# Boost_LM5123.net
KiCad netlist of a schematic drawn in Altium Designer
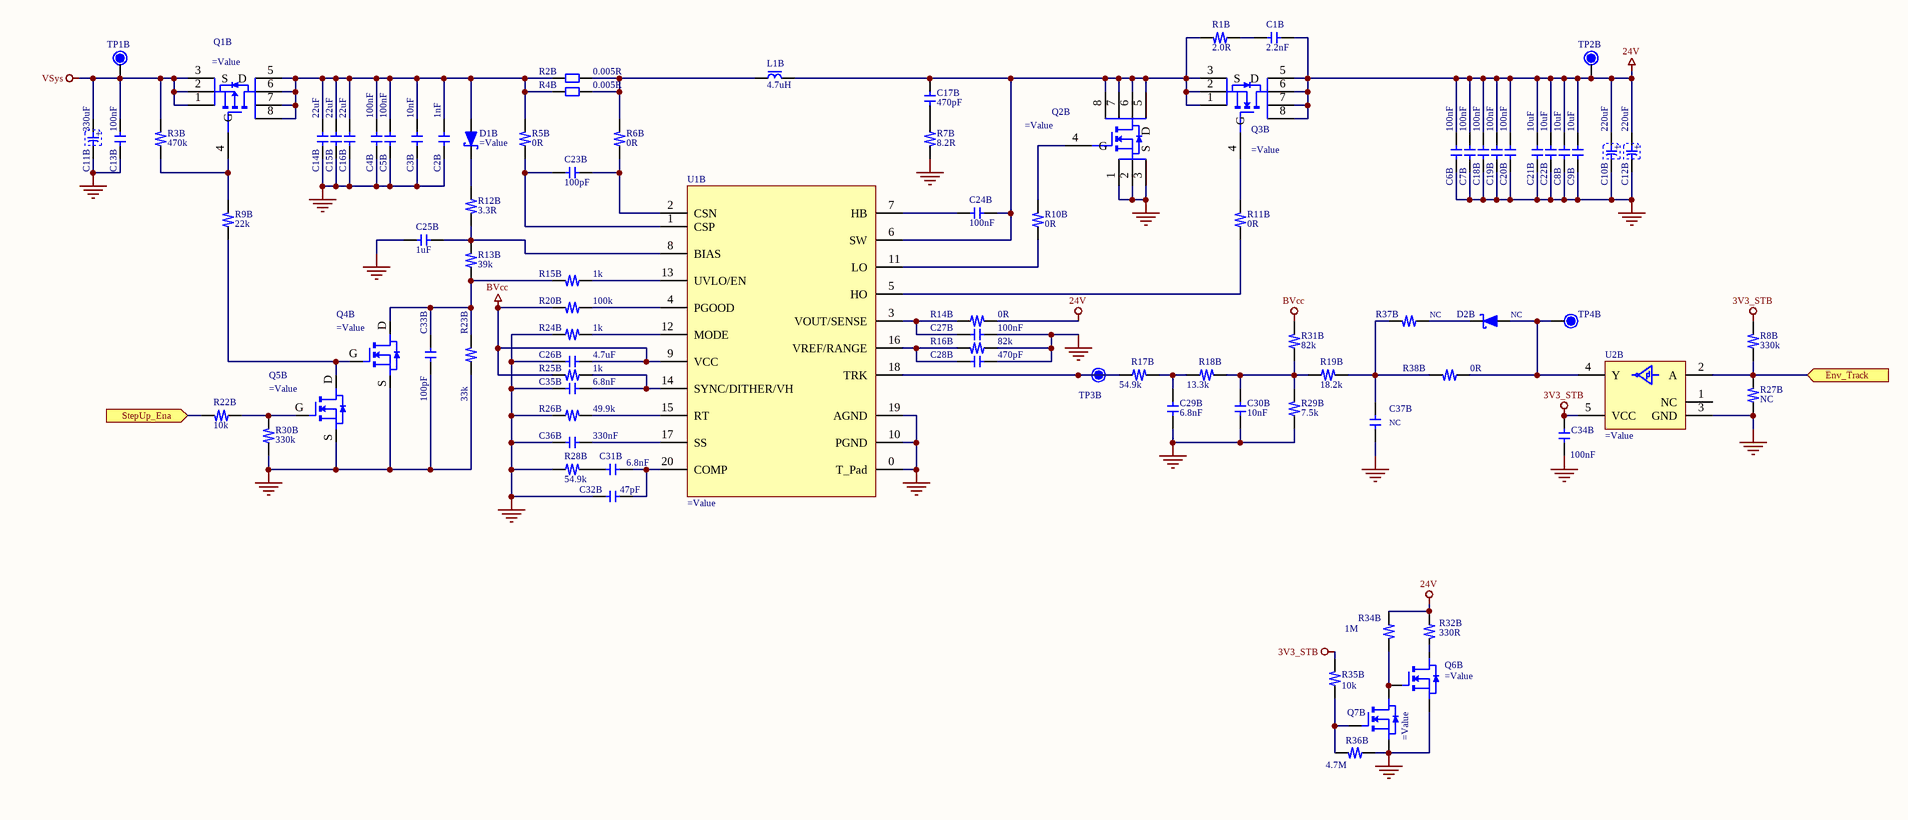
[diagram p0: Boost_LM5123.SchDoc]

(export (version "E")
  (design (tool "Eeschema 10.0.6"))
  (components
    (comp (ref "C1B")
      (value "2.2nF")
      (footprint "C0603X100")
      (description "PSHF SMD M CAP 2.2nF 50V ±10% 0603 X7R")
      (fields (field (name "MANUFACTURER") "Multi Sourced") (field (name "TOLERANCE") "±10%"))
      (libsource (lib "altium-import") (part "root_2_CAP1_"))
    )
    (comp (ref "C2B")
      (value "1nF")
      (footprint "C0603X100")
      (description "PSHF SMD M CAP 1nF 50V ±10% 0603 X7R")
      (fields (field (name "MANUFACTURER") "Multi Sourced") (field (name "TOLERANCE") "±10%"))
      (libsource (lib "altium-import") (part "root_1_CAP1_"))
    )
    (comp (ref "C3B")
      (value "10nF")
      (footprint "C0603X100")
      (description "PSHF SMD M CAP 10nF 50V ±10% 0603 X7R")
      (fields (field (name "MANUFACTURER") "Multi Sourced") (field (name "TOLERANCE") "±10%"))
      (libsource (lib "altium-import") (part "root_1_CAP1_"))
    )
    (comp (ref "C4B")
      (value "100nF")
      (footprint "C0603X100")
      (description "PSHF SMD M CAP 100nF 25V ±10% 0603 X7R")
      (fields (field (name "MANUFACTURER") "Multi Sourced") (field (name "TOLERANCE") "±10%"))
      (libsource (lib "altium-import") (part "root_3_CAP1_"))
    )
    (comp (ref "C5B")
      (value "100nF")
      (footprint "C0603X100")
      (description "PSHF SMD M CAP 100nF 25V ±10% 0603 X7R")
      (fields (field (name "MANUFACTURER") "Multi Sourced") (field (name "TOLERANCE") "±10%"))
      (libsource (lib "altium-import") (part "root_3_CAP1_"))
    )
    (comp (ref "C6B")
      (value "100nF")
      (footprint "C0603X100")
      (description "PSHF SMD M CAP 100nF 50V ±10% 0603 X7R")
      (fields (field (name "MANUFACTURER") "Multi Sourced") (field (name "TOLERANCE") "±10%"))
      (libsource (lib "altium-import") (part "root_1_CAP1_"))
    )
    (comp (ref "C7B")
      (value "100nF")
      (footprint "C0603X100")
      (description "PSHF SMD M CAP 100nF 50V ±10% 0603 X7R")
      (fields (field (name "MANUFACTURER") "Multi Sourced") (field (name "TOLERANCE") "±10%"))
      (libsource (lib "altium-import") (part "root_1_CAP1_"))
    )
    (comp (ref "C8B")
      (value "10uF")
      (footprint "C1206")
      (description "PSHF SMD M CAP 10uF 50V ±10% 1206 X5R")
      (fields (field (name "MANUFACTURER") "Multi Sourced") (field (name "TOLERANCE") "±10%"))
      (libsource (lib "altium-import") (part "root_1_CAP1_"))
    )
    (comp (ref "C9B")
      (value "10uF")
      (footprint "C1206")
      (description "PSHF SMD M CAP 10uF 50V ±10% 1206 X5R")
      (fields (field (name "MANUFACTURER") "Multi Sourced") (field (name "TOLERANCE") "±10%"))
      (libsource (lib "altium-import") (part "root_1_CAP1_"))
    )
    (comp (ref "C10B")
      (value "220uF")
      (footprint "ECAP_SMD_800X1000")
      (description "SMD COND ELECT 220μF 35V ±20% 105°C SHOUKE")
      (fields (field (name "MANUFACTURER") "Multi-Sourced") (field (name "TOLERANCE") "±20%"))
      (libsource (lib "altium-import") (part "root_3_ECAP2_"))
    )
    (comp (ref "C11B")
      (value "330uF")
      (footprint "E_CAP_SMD_10%2A10.2")
      (description "GPHF SMD COND ELECT 330μF 35V ±20% -40-+105℃ 10x10.5mm")
      (fields (field (name "MANUFACTURER") "Multi-Sourced") (field (name "TOLERANCE") "±20%"))
      (libsource (lib "altium-import") (part "root_3_ECAP2_"))
    )
    (comp (ref "C12B")
      (value "220uF")
      (footprint "ECAP_SMD_800X1000")
      (description "SMD COND ELECT 220μF 35V ±20% 105°C SHOUKE")
      (fields (field (name "MANUFACTURER") "Multi-Sourced") (field (name "TOLERANCE") "±20%"))
      (libsource (lib "altium-import") (part "root_3_ECAP2_"))
    )
    (comp (ref "C13B")
      (value "100nF")
      (footprint "C0603X100")
      (description "PSHF SMD M CAP 100nF 25V ±10% 0603 X7R")
      (fields (field (name "MANUFACTURER") "Multi Sourced") (field (name "TOLERANCE") "±10%"))
      (libsource (lib "altium-import") (part "root_1_CAP1_"))
    )
    (comp (ref "C14B")
      (value "22uF")
      (footprint "C1206")
      (description "PSHF SMD M CAP 22uF 25V ±20% 1206 X5R")
      (fields (field (name "MANUFACTURER") "Multi Sourced") (field (name "TOLERANCE") "±20%"))
      (libsource (lib "altium-import") (part "root_1_CAP1_"))
    )
    (comp (ref "C15B")
      (value "22uF")
      (footprint "C1206")
      (description "PSHF SMD M CAP 22uF 25V ±20% 1206 X5R")
      (fields (field (name "MANUFACTURER") "Multi Sourced") (field (name "TOLERANCE") "±20%"))
      (libsource (lib "altium-import") (part "root_1_CAP1_"))
    )
    (comp (ref "C16B")
      (value "22uF")
      (footprint "C1206")
      (description "PSHF SMD M CAP 22uF 25V ±20% 1206 X5R")
      (fields (field (name "MANUFACTURER") "Multi Sourced") (field (name "TOLERANCE") "±20%"))
      (libsource (lib "altium-import") (part "root_1_CAP1_"))
    )
    (comp (ref "C17B")
      (value "470pF")
      (footprint "C0603X80")
      (description "PSHF SMD M CAP 470pF 50V ±5% 0603 NPO")
      (fields (field (name "MANUFACTURER") "Multi Sourced") (field (name "TOLERANCE") "±5%"))
      (libsource (lib "altium-import") (part "root_3_CAP1_"))
    )
    (comp (ref "C18B")
      (value "100nF")
      (footprint "C0603X100")
      (description "PSHF SMD M CAP 100nF 50V ±10% 0603 X7R")
      (fields (field (name "MANUFACTURER") "Multi Sourced") (field (name "TOLERANCE") "±10%"))
      (libsource (lib "altium-import") (part "root_1_CAP1_"))
    )
    (comp (ref "C19B")
      (value "100nF")
      (footprint "C0603X100")
      (description "PSHF SMD M CAP 100nF 50V ±10% 0603 X7R")
      (fields (field (name "MANUFACTURER") "Multi Sourced") (field (name "TOLERANCE") "±10%"))
      (libsource (lib "altium-import") (part "root_1_CAP1_"))
    )
    (comp (ref "C20B")
      (value "100nF")
      (footprint "C0603X100")
      (description "PSHF SMD M CAP 100nF 50V ±10% 0603 X7R")
      (fields (field (name "MANUFACTURER") "Multi Sourced") (field (name "TOLERANCE") "±10%"))
      (libsource (lib "altium-import") (part "root_1_CAP1_"))
    )
    (comp (ref "C21B")
      (value "10uF")
      (footprint "C1206")
      (description "PSHF SMD M CAP 10uF 50V ±10% 1206 X5R")
      (fields (field (name "MANUFACTURER") "Multi Sourced") (field (name "TOLERANCE") "±10%"))
      (libsource (lib "altium-import") (part "root_1_CAP1_"))
    )
    (comp (ref "C22B")
      (value "10uF")
      (footprint "C1206")
      (description "PSHF SMD M CAP 10uF 50V ±10% 1206 X5R")
      (fields (field (name "MANUFACTURER") "Multi Sourced") (field (name "TOLERANCE") "±10%"))
      (libsource (lib "altium-import") (part "root_1_CAP1_"))
    )
    (comp (ref "C23B")
      (value "100pF")
      (footprint "C0603X80")
      (description "PSHF SMD M CAP 100pF 50V ±10% 0603 X7R")
      (fields (field (name "MANUFACTURER") "Multi Sourced") (field (name "TOLERANCE") "±10%"))
      (libsource (lib "altium-import") (part "root_0_CAP1_"))
    )
    (comp (ref "C24B")
      (value "100nF")
      (footprint "C0603X100")
      (description "GPHF SMD M CAP 100nF 50V ±10% 0603 X7R")
      (fields (field (name "MANUFACTURER") "Multi Sourced") (field (name "TOLERANCE") "±10%"))
      (libsource (lib "altium-import") (part "root_2_CAP1_"))
    )
    (comp (ref "C25B")
      (value "1uF")
      (footprint "C0603X105")
      (description "PSHF SMD M CAP 1uF 25V ±10% 0603 X7R")
      (fields (field (name "MANUFACTURER") "Multi Sourced") (field (name "TOLERANCE") "±10%"))
      (libsource (lib "altium-import") (part "root_2_CAP1_"))
    )
    (comp (ref "C26B")
      (value "4.7uF")
      (footprint "C0805_145")
      (description "PSHF SMD M CAP 4.7uF 25V ±10% 0805 X7R")
      (fields (field (name "MANUFACTURER") "Multi Sourced") (field (name "TOLERANCE") "±10%"))
      (libsource (lib "altium-import") (part "root_2_CAP1_"))
    )
    (comp (ref "C27B")
      (value "100nF")
      (footprint "C0603X100")
      (description "GPHF SMD M CAP 100nF 50V ±10% 0603 X7R")
      (fields (field (name "MANUFACTURER") "Multi Sourced") (field (name "TOLERANCE") "±10%"))
      (libsource (lib "altium-import") (part "root_0_CAP1_"))
    )
    (comp (ref "C28B")
      (value "470pF")
      (footprint "C0603X80")
      (description "PSHF SMD M CAP 470pF 50V ±5% 0603 NPO")
      (fields (field (name "MANUFACTURER") "Multi Sourced") (field (name "TOLERANCE") "±5%"))
      (libsource (lib "altium-import") (part "root_0_CAP1_"))
    )
    (comp (ref "C29B")
      (value "6.8nF")
      (footprint "C0603X100")
      (description "PSHF SMD M CAP 6.8nF 50V ±10% 0603 X7R")
      (fields (field (name "MANUFACTURER") "Multi Sourced") (field (name "TOLERANCE") "±10%"))
      (libsource (lib "altium-import") (part "root_3_CAP1_"))
    )
    (comp (ref "C30B")
      (value "10nF")
      (footprint "C0603X100")
      (description "PSHF SMD M CAP 10nF 50V ±10% 0603 X7R")
      (fields (field (name "MANUFACTURER") "Multi Sourced") (field (name "TOLERANCE") "±10%"))
      (libsource (lib "altium-import") (part "root_3_CAP1_"))
    )
    (comp (ref "C31B")
      (value "6.8nF")
      (footprint "C0603X100")
      (description "PSHF SMD M CAP 6.8nF 50V ±10% 0603 X7R")
      (fields (field (name "MANUFACTURER") "Multi Sourced") (field (name "TOLERANCE") "±10%"))
      (libsource (lib "altium-import") (part "root_0_CAP1_"))
    )
    (comp (ref "C32B")
      (value "47pF")
      (footprint "C0603X80")
      (description "PSHF SMD M CAP 47pF 50V ±5% 0603 NPO")
      (fields (field (name "MANUFACTURER") "Multi Sourced") (field (name "TOLERANCE") "±5%"))
      (libsource (lib "altium-import") (part "root_2_CAP1_"))
    )
    (comp (ref "C33B")
      (value "100pF")
      (footprint "C0603X80")
      (description "PSHF SMD M CAP 100pF 50V ±10% 0603 X7R")
      (fields (field (name "MANUFACTURER") "Multi Sourced") (field (name "TOLERANCE") "±10%"))
      (libsource (lib "altium-import") (part "root_3_CAP1_"))
    )
    (comp (ref "C34B")
      (value "100nF")
      (footprint "C0603X100")
      (description "PSHF SMD M CAP 100nF 25V ±10% 0603 X7R")
      (fields (field (name "MANUFACTURER") "Multi Sourced") (field (name "TOLERANCE") "±10%"))
      (libsource (lib "altium-import") (part "root_1_CAP1_"))
    )
    (comp (ref "C35B")
      (value "6.8nF")
      (footprint "C0603X100")
      (description "PSHF SMD M CAP 6.8nF 50V ±10% 0603 X7R")
      (fields (field (name "MANUFACTURER") "Multi Sourced") (field (name "TOLERANCE") "±10%"))
      (libsource (lib "altium-import") (part "root_2_CAP1_"))
    )
    (comp (ref "C36B")
      (value "330nF")
      (footprint "C0603X105")
      (description "SMD M CAP 330nF 50V ±10% 0603 X7R")
      (fields (field (name "MANUFACTURER") "Multi Sourced") (field (name "TOLERANCE") "±10%"))
      (libsource (lib "altium-import") (part "root_2_CAP1_"))
    )
    (comp (ref "C37B")
      (value "1uF")
      (footprint "C0603X105")
      (description "GPHF SMD M CAP 1uF 10V ±10% 0603 X7R")
      (fields (field (name "TOLERANCE") "±10%") (field (name "MANUFACTURER") "Multi Sourced"))
      (libsource (lib "altium-import") (part "root_1_CAP1_"))
    )
    (comp (ref "D1B")
      (value "~")
      (footprint "SOD-123")
      (description "PS SMD DIODE 2P SOD-123 B5819W CJ")
      (fields (field (name "MANUFACTURER") "[CJ]") (field (name "VOLTAGE") "40V"))
      (libsource (lib "altium-import") (part "root_3_DIODE_SCHOTTKY1_"))
    )
    (comp (ref "D2B")
      (value "~")
      (footprint "SOD-323")
      (description "GP SMD DIODE 2P 30V SOD323 BAT54WS PANJIT")
      (fields (field (name "MANUFACTURER") "PANJIT") (field (name "VOLTAGE") "30V"))
      (libsource (lib "altium-import") (part "root_0_mirrored_DIODE_SCHOTTKY1_"))
    )
    (comp (ref "L1B")
      (value "4.7uH")
      (footprint "IND_SMD_YT_SQU_L135XW126XH57")
      (description "SMD INDUCTOR 4.7μH 100KHz NORM")
      (fields (field (name "MANUFACTURER") "CET CHAMPI") (field (name "TOLERANCE") "7:20%"))
      (libsource (lib "altium-import") (part "root_0_INDUCTOR1_"))
    )
    (comp (ref "Q1B")
      (value "~")
      (footprint "DFN8_500X600X100_127_A")
      (description "SMD FET 8P 30V PDFN5x6-8L JMTG080P03A JJW")
      (fields (field (name "MANUFACTURER") "JJW") (field (name "VOLTAGE") "30"))
      (libsource (lib "altium-import") (part "root_1_mirrored_P-MOS2_8Pin_"))
    )
    (comp (ref "Q2B")
      (value "~")
      (footprint "DFN8_500X600X100_127_A")
      (description "SMD FET 8P 40V PDFN5x6-8L JMTG60N04B JJW")
      (fields (field (name "MANUFACTURER") "JJW") (field (name "VOLTAGE") "40"))
      (libsource (lib "altium-import") (part "root_0_N-MOS2_8Pin_"))
    )
    (comp (ref "Q3B")
      (value "~")
      (footprint "DFN8_500X600X100_127_A")
      (description "SMD FET 8P 40V PDFN5x6-8L JMTG60N04B JJW")
      (fields (field (name "MANUFACTURER") "JJW") (field (name "VOLTAGE") "40"))
      (libsource (lib "altium-import") (part "root_1_mirrored_N-MOS2_8Pin_"))
    )
    (comp (ref "Q4B")
      (value "~")
      (footprint "SOT23-GSD")
      (description "GP SMD FET 3P SOT23 2N7002K CTE")
      (fields (field (name "MANUFACTURER") "CTE") (field (name "VOLTAGE") "60V"))
      (libsource (lib "") (part "root_0_N-MOS1__1"))
    )
    (comp (ref "Q5B")
      (value "~")
      (footprint "SOT23-GSD")
      (description "GP SMD FET 3P SOT23 2N7002K CTE")
      (fields (field (name "MANUFACTURER") "CTE") (field (name "VOLTAGE") "60V"))
      (libsource (lib "") (part "root_0_N-MOS1__1"))
    )
    (comp (ref "Q6B")
      (value "~")
      (footprint "SOT23-GSD")
      (description "GP SMD FET 3P SOT23 2N7002K CTE")
      (fields (field (name "MANUFACTURER") "CTE") (field (name "VOLTAGE") "60V"))
      (libsource (lib "altium-import") (part "root_0_N-MOS1_"))
    )
    (comp (ref "Q7B")
      (value "~")
      (footprint "SOT23-GSD")
      (description "GP SMD FET 3P SOT23 2N7002K CTE")
      (fields (field (name "MANUFACTURER") "CTE") (field (name "VOLTAGE") "60V"))
      (libsource (lib "altium-import") (part "root_0_N-MOS1_"))
    )
    (comp (ref "R1B")
      (value "2.0R")
      (footprint "R0805")
      (description "PS SMD RES. 2OHM 1/8W 5% 0805")
      (fields (field (name "TOLERANCE") "1%") (field (name "MANUFACTURER") "Multi-Sourced"))
      (libsource (lib "altium-import") (part "root_0_RES1_"))
    )
    (comp (ref "R2B")
      (value "0.005R")
      (footprint "R1206")
      (description "SMD METAL FILM RES. 5mohm 1W 1% 1206 WALTER")
      (fields (field (name "TOLERANCE") "1%") (field (name "MANUFACTURER") "WALTER"))
      (libsource (lib "altium-import") (part "root_0_RES4_"))
    )
    (comp (ref "R3B")
      (value "470k")
      (footprint "R0603")
      (description "PS SMD RES. 470KOHM 1/10W 1% 0603")
      (fields (field (name "TOLERANCE") "1%") (field (name "MANUFACTURER") "Multi-Sourced"))
      (libsource (lib "altium-import") (part "root_3_RES1_"))
    )
    (comp (ref "R4B")
      (value "0.005R")
      (footprint "R1206")
      (description "SMD METAL FILM RES. 5mohm 1W 1% 1206 WALTER")
      (fields (field (name "TOLERANCE") "1%") (field (name "MANUFACTURER") "WALTER"))
      (libsource (lib "altium-import") (part "root_0_RES4_"))
    )
    (comp (ref "R5B")
      (value "0R")
      (footprint "R0603")
      (description "PS SMD RES. 0OHM 1/10W 5% 0603")
      (fields (field (name "TOLERANCE") "1%") (field (name "MANUFACTURER") "Multi-Sourced"))
      (libsource (lib "altium-import") (part "root_3_RES1_"))
    )
    (comp (ref "R6B")
      (value "0R")
      (footprint "R0603")
      (description "PS SMD RES. 0OHM 1/10W 5% 0603")
      (fields (field (name "TOLERANCE") "1%") (field (name "MANUFACTURER") "Multi-Sourced"))
      (libsource (lib "altium-import") (part "root_3_RES1_"))
    )
    (comp (ref "R7B")
      (value "8.2R")
      (footprint "R0805")
      (description "SMD RES. 8.2Ohm 1/8W 1% 0805")
      (fields (field (name "TOLERANCE") "1%") (field (name "MANUFACTURER") "Multi-Sourced"))
      (libsource (lib "altium-import") (part "root_1_RES1_"))
    )
    (comp (ref "R8B")
      (value "330k")
      (footprint "R0603")
      (description "PS SMD RES. 330KOHM 1/10W 1% 0603")
      (fields (field (name "TOLERANCE") "1%") (field (name "MANUFACTURER") "Multi-Sourced"))
      (libsource (lib "altium-import") (part "root_3_RES1_"))
    )
    (comp (ref "R9B")
      (value "22k")
      (footprint "R0603")
      (description "PS SMD RES. 22KOHM 1/10W 1% 0603")
      (fields (field (name "TOLERANCE") "1%") (field (name "MANUFACTURER") "Multi-Sourced"))
      (libsource (lib "altium-import") (part "root_3_RES1_"))
    )
    (comp (ref "R10B")
      (value "0R")
      (footprint "R0603")
      (description "PS SMD RES. 0OHM 1/10W 5% 0603")
      (fields (field (name "TOLERANCE") "1%") (field (name "MANUFACTURER") "Multi-Sourced"))
      (libsource (lib "altium-import") (part "root_1_mirrored_RES1_"))
    )
    (comp (ref "R11B")
      (value "0R")
      (footprint "R0603")
      (description "PS SMD RES. 0OHM 1/10W 5% 0603")
      (fields (field (name "TOLERANCE") "1%") (field (name "MANUFACTURER") "Multi-Sourced"))
      (libsource (lib "altium-import") (part "root_1_mirrored_RES1_"))
    )
    (comp (ref "R12B")
      (value "3.3R")
      (footprint "R0603")
      (description "PS SMD RES. 3.3OHM 1/10W 1% 0603")
      (fields (field (name "TOLERANCE") "1%") (field (name "MANUFACTURER") "Multi-Sourced"))
      (libsource (lib "altium-import") (part "root_1_RES1_"))
    )
    (comp (ref "R13B")
      (value "39k")
      (footprint "R0603")
      (description "PS SMD RES. 39KOHM 1/10W 1% 0603")
      (fields (field (name "TOLERANCE") "1%") (field (name "MANUFACTURER") "Multi-Sourced"))
      (libsource (lib "altium-import") (part "root_3_RES1_"))
    )
    (comp (ref "R14B")
      (value "0R")
      (footprint "R0603")
      (description "PS SMD RES. 0OHM 1/10W 5% 0603")
      (fields (field (name "TOLERANCE") "1%") (field (name "MANUFACTURER") "Multi-Sourced"))
      (libsource (lib "altium-import") (part "root_2_RES1_"))
    )
    (comp (ref "R15B")
      (value "1k")
      (footprint "R0603")
      (description "PS SMD RES. 1KOHM 1/10W 1% 0603")
      (fields (field (name "TOLERANCE") "1%") (field (name "MANUFACTURER") "Multi-Sourced"))
      (libsource (lib "altium-import") (part "root_0_RES1_"))
    )
    (comp (ref "R16B")
      (value "82k")
      (footprint "R0603")
      (description "PS SMD RES. 82KOHM 1/10W 1% 0603")
      (fields (field (name "TOLERANCE") "5%") (field (name "MANUFACTURER") "Multi-Sourced"))
      (libsource (lib "altium-import") (part "root_0_RES1_"))
    )
    (comp (ref "R17B")
      (value "54.9k")
      (footprint "R0603")
      (description "SMD RES. 54.9KOhm 1/10W 1% 0603")
      (fields (field (name "TOLERANCE") "5%") (field (name "MANUFACTURER") "Multi-Sourced"))
      (libsource (lib "altium-import") (part "root_2_RES1_"))
    )
    (comp (ref "R18B")
      (value "13.3k")
      (footprint "R0603")
      (description "PS SMD RES. 13.3KOHM 1/10W 1% 0603")
      (fields (field (name "TOLERANCE") "5%") (field (name "MANUFACTURER") "Multi-Sourced"))
      (libsource (lib "altium-import") (part "root_2_RES1_"))
    )
    (comp (ref "R19B")
      (value "18.2k")
      (footprint "R0603")
      (description "GPHF SMD RES. 18.2KOHM 1/10W 1% 0603")
      (fields (field (name "TOLERANCE") "1%") (field (name "MANUFACTURER") "Multi-Sourced"))
      (libsource (lib "altium-import") (part "root_2_RES1_"))
    )
    (comp (ref "R20B")
      (value "100k")
      (footprint "R0603")
      (description "PS SMD RES. 100KOHM 1/10W 1% 0603")
      (fields (field (name "TOLERANCE") "1%") (field (name "MANUFACTURER") "Multi-Sourced"))
      (libsource (lib "altium-import") (part "root_0_RES1_"))
    )
    (comp (ref "R22B")
      (value "10k")
      (footprint "R0603")
      (description "PS SMD RES. 10KOHM 1/10W 1% 0603")
      (fields (field (name "TOLERANCE") "1%") (field (name "MANUFACTURER") "Multi-Sourced"))
      (libsource (lib "altium-import") (part "root_0_RES1_"))
    )
    (comp (ref "R23B")
      (value "33k")
      (footprint "R0603")
      (description "PS SMD RES. 33KOHM 1/10W 1% 0603")
      (fields (field (name "TOLERANCE") "1%") (field (name "MANUFACTURER") "Multi-Sourced"))
      (libsource (lib "altium-import") (part "root_3_RES1_"))
    )
    (comp (ref "R24B")
      (value "1k")
      (footprint "R0603")
      (description "PS SMD RES. 1KOHM 1/10W 1% 0603")
      (fields (field (name "TOLERANCE") "1%") (field (name "MANUFACTURER") "Multi-Sourced"))
      (libsource (lib "altium-import") (part "root_2_RES1_"))
    )
    (comp (ref "R25B")
      (value "1k")
      (footprint "R0603")
      (description "PS SMD RES. 1KOHM 1/10W 1% 0603")
      (fields (field (name "TOLERANCE") "1%") (field (name "MANUFACTURER") "Multi-Sourced"))
      (libsource (lib "altium-import") (part "root_0_RES1_"))
    )
    (comp (ref "R26B")
      (value "49.9k")
      (footprint "R0603")
      (description "PS SMD RES. 49.9KOHM 1/10W 1% 0603")
      (fields (field (name "TOLERANCE") "1%") (field (name "MANUFACTURER") "Multi-Sourced"))
      (libsource (lib "altium-import") (part "root_2_RES1_"))
    )
    (comp (ref "R27B")
      (value "NC")
      (footprint "R0603")
      (description "PS SMD RES. 100KOHM 1/10W 1% 0603")
      (fields (field (name "TOLERANCE") "1%") (field (name "MANUFACTURER") "Multi-Sourced"))
      (libsource (lib "altium-import") (part "root_3_RES1_"))
    )
    (comp (ref "R28B")
      (value "54.9k")
      (footprint "R0603")
      (description "SMD RES. 54.9KOhm 1/10W 1% 0603")
      (fields (field (name "TOLERANCE") "1%") (field (name "MANUFACTURER") "Multi-Sourced"))
      (libsource (lib "altium-import") (part "root_2_RES1_"))
    )
    (comp (ref "R29B")
      (value "7.5k")
      (footprint "R0603")
      (description "GPHF SMD RES. 7.5KOHM 1/10W 1% 0603")
      (fields (field (name "TOLERANCE") "1%") (field (name "MANUFACTURER") "Multi-Sourced"))
      (libsource (lib "altium-import") (part "root_3_RES1_"))
    )
    (comp (ref "R30B")
      (value "330k")
      (footprint "R0603")
      (description "PS SMD RES. 330KOHM 1/10W 1% 0603")
      (fields (field (name "TOLERANCE") "1%") (field (name "MANUFACTURER") "Multi-Sourced"))
      (libsource (lib "altium-import") (part "root_3_RES1_"))
    )
    (comp (ref "R31B")
      (value "82k")
      (footprint "R0603")
      (description "GPHF SMD RES. 82KOHM 1/10W 1% 0603")
      (fields (field (name "TOLERANCE") "1%") (field (name "MANUFACTURER") "Multi-Sourced"))
      (libsource (lib "altium-import") (part "root_3_RES1_"))
    )
    (comp (ref "R32B")
      (value "330R")
      (footprint "R1206")
      (description "PS SMD RES. 330OHM 1/4W 5% 1206")
      (fields (field (name "TOLERANCE") "5%") (field (name "MANUFACTURER") "Multi-Sourced"))
      (libsource (lib "altium-import") (part "root_1_RES1_"))
    )
    (comp (ref "R34B")
      (value "1M")
      (footprint "R0603")
      (description "PS SMD RES. 1MOHM 1/10W 5% 0603")
      (fields (field (name "TOLERANCE") "5%") (field (name "MANUFACTURER") "Multi-Sourced"))
      (libsource (lib "altium-import") (part "root_1_RES1_"))
    )
    (comp (ref "R35B")
      (value "10k")
      (footprint "R0603")
      (description "PS SMD RES. 10KOHM 1/10W 1% 0603")
      (fields (field (name "TOLERANCE") "1%") (field (name "MANUFACTURER") "Multi-Sourced"))
      (libsource (lib "altium-import") (part "root_3_RES1_"))
    )
    (comp (ref "R36B")
      (value "4.7M")
      (footprint "R0603")
      (description "PS SMD RES. 4.7MOHM 1/10W 5% 0603")
      (fields (field (name "TOLERANCE") "5%") (field (name "MANUFACTURER") "Multi-Sourced"))
      (libsource (lib "altium-import") (part "root_0_RES1_"))
    )
    (comp (ref "R37B")
      (value "180R")
      (footprint "R0603")
      (description "GPHF SMD RES. 180OHM 1/10W 5% 0603")
      (fields (field (name "MANUFACTURER") "Multi-Sourced") (field (name "TOLERANCE") "5%"))
      (libsource (lib "altium-import") (part "root_0_RES1_"))
    )
    (comp (ref "R38B")
      (value "0R")
      (footprint "R0603")
      (description "GPHF SMD RES. 0OHM 1/10W 5% 0603")
      (fields (field (name "MANUFACTURER") "Multi-Sourced") (field (name "TOLERANCE") "5%"))
      (libsource (lib "altium-import") (part "root_0_RES1_"))
    )
    (comp (ref "TP1B")
      (value "TP_T_60_40")
      (footprint "TP_T_60_40")
      (description "Test Point")
      (libsource (lib "altium-import") (part "root_1_TP_"))
    )
    (comp (ref "TP2B")
      (value "TP_T_60_40")
      (footprint "TP_T_60_40")
      (description "Test Point")
      (libsource (lib "altium-import") (part "root_1_TP_"))
    )
    (comp (ref "TP3B")
      (value "TP_T_60_40")
      (footprint "TP_T_60_40")
      (description "Test Point")
      (libsource (lib "altium-import") (part "root_0_TP_"))
    )
    (comp (ref "TP4B")
      (value "TP_T_60_40")
      (footprint "TP_T_60_40")
      (description "Test Point")
      (libsource (lib "altium-import") (part "root_0_TP_"))
    )
    (comp (ref "U1B")
      (value "~")
      (footprint "QFN20_350X350X100_50_P200X200")
      (description "SMD IC 20P VQFN LM51231QRGRRQ1 TI")
      (fields (field (name "MANUFACTURER") "TI") (field (name "PART_NUMBER") "LM51231QRGRRQ1"))
      (libsource (lib "altium-import") (part "root_0_LM51231_"))
    )
    (comp (ref "U2B")
      (value "~")
      (footprint "SOT23-5")
      (description "GP SMD IC 5P SOT23 SGM7SZ14YN5G/TR SGMICRO")
      (fields (field (name "MANUFACTURER") "[SGMICRO]") (field (name "PART_NUMBER") "SGM7SZ14YN5G/TR"))
      (libsource (lib "altium-import") (part "root_0_mirrored_74xx1G14_"))
    )
  )
  (nets
    (net (code "1") (name "/Env_Track") (class "Default")
      (node (ref "R27B") (pin "1") (pinfunction "1_1") (pintype "passive"))
      (node (ref "R8B") (pin "2") (pinfunction "2_2") (pintype "passive"))
      (node (ref "U2B") (pin "2") (pinfunction "A_2") (pintype "passive"))
    )
    (net (code "2") (name "/StepUp_Ena") (class "Default")
      (node (ref "R22B") (pin "1") (pinfunction "1_1") (pintype "passive"))
    )
    (net (code "3") (name "3V3_STB") (class "Default")
      (node (ref "C34B") (pin "2") (pinfunction "2_2") (pintype "passive"))
      (node (ref "R35B") (pin "1") (pinfunction "1_1") (pintype "passive"))
      (node (ref "R8B") (pin "1") (pinfunction "1_1") (pintype "passive"))
      (node (ref "U2B") (pin "5") (pinfunction "VCC_5") (pintype "passive"))
    )
    (net (code "4") (name "24V") (class "Default")
      (node (ref "C10B") (pin "1") (pinfunction "1_1") (pintype "passive"))
      (node (ref "C12B") (pin "1") (pinfunction "1_1") (pintype "passive"))
      (node (ref "C18B") (pin "2") (pinfunction "2_2") (pintype "passive"))
      (node (ref "C19B") (pin "2") (pinfunction "2_2") (pintype "passive"))
      (node (ref "C1B") (pin "1") (pinfunction "1_1") (pintype "passive"))
      (node (ref "C20B") (pin "2") (pinfunction "2_2") (pintype "passive"))
      (node (ref "C21B") (pin "2") (pinfunction "2_2") (pintype "passive"))
      (node (ref "C22B") (pin "2") (pinfunction "2_2") (pintype "passive"))
      (node (ref "C6B") (pin "2") (pinfunction "2_2") (pintype "passive"))
      (node (ref "C7B") (pin "2") (pinfunction "2_2") (pintype "passive"))
      (node (ref "C8B") (pin "2") (pinfunction "2_2") (pintype "passive"))
      (node (ref "C9B") (pin "2") (pinfunction "2_2") (pintype "passive"))
      (node (ref "Q3B") (pin "5") (pinfunction "D_5") (pintype "passive"))
      (node (ref "Q3B") (pin "6") (pinfunction "D_6") (pintype "passive"))
      (node (ref "Q3B") (pin "7") (pinfunction "D_7") (pintype "passive"))
      (node (ref "Q3B") (pin "8") (pinfunction "D_8") (pintype "passive"))
      (node (ref "R14B") (pin "1") (pinfunction "1_1") (pintype "passive"))
      (node (ref "R32B") (pin "2") (pinfunction "2_2") (pintype "passive"))
      (node (ref "R34B") (pin "2") (pinfunction "2_2") (pintype "passive"))
      (node (ref "TP2B") (pin "1") (pinfunction "1_1") (pintype "passive"))
    )
    (net (code "5") (name "BVcc") (class "Default")
      (node (ref "C26B") (pin "1") (pinfunction "1_1") (pintype "passive"))
      (node (ref "R20B") (pin "1") (pinfunction "1_1") (pintype "passive"))
      (node (ref "R25B") (pin "1") (pinfunction "1_1") (pintype "passive"))
      (node (ref "R31B") (pin "1") (pinfunction "1_1") (pintype "passive"))
      (node (ref "U1B") (pin "9") (pinfunction "VCC_9") (pintype "passive"))
    )
    (net (code "6") (name "GND") (class "Default")
      (node (ref "C10B") (pin "2") (pinfunction "2_2") (pintype "passive"))
      (node (ref "C11B") (pin "2") (pinfunction "2_2") (pintype "passive"))
      (node (ref "C12B") (pin "2") (pinfunction "2_2") (pintype "passive"))
      (node (ref "C13B") (pin "1") (pinfunction "1_1") (pintype "passive"))
      (node (ref "C14B") (pin "1") (pinfunction "1_1") (pintype "passive"))
      (node (ref "C15B") (pin "1") (pinfunction "1_1") (pintype "passive"))
      (node (ref "C16B") (pin "1") (pinfunction "1_1") (pintype "passive"))
      (node (ref "C18B") (pin "1") (pinfunction "1_1") (pintype "passive"))
      (node (ref "C19B") (pin "1") (pinfunction "1_1") (pintype "passive"))
      (node (ref "C20B") (pin "1") (pinfunction "1_1") (pintype "passive"))
      (node (ref "C21B") (pin "1") (pinfunction "1_1") (pintype "passive"))
      (node (ref "C22B") (pin "1") (pinfunction "1_1") (pintype "passive"))
      (node (ref "C25B") (pin "2") (pinfunction "2_2") (pintype "passive"))
      (node (ref "C26B") (pin "2") (pinfunction "2_2") (pintype "passive"))
      (node (ref "C27B") (pin "2") (pinfunction "2_2") (pintype "passive"))
      (node (ref "C28B") (pin "2") (pinfunction "2_2") (pintype "passive"))
      (node (ref "C29B") (pin "2") (pinfunction "2_2") (pintype "passive"))
      (node (ref "C2B") (pin "1") (pinfunction "1_1") (pintype "passive"))
      (node (ref "C30B") (pin "2") (pinfunction "2_2") (pintype "passive"))
      (node (ref "C32B") (pin "2") (pinfunction "2_2") (pintype "passive"))
      (node (ref "C33B") (pin "2") (pinfunction "2_2") (pintype "passive"))
      (node (ref "C34B") (pin "1") (pinfunction "1_1") (pintype "passive"))
      (node (ref "C35B") (pin "2") (pinfunction "2_2") (pintype "passive"))
      (node (ref "C36B") (pin "2") (pinfunction "2_2") (pintype "passive"))
      (node (ref "C37B") (pin "1") (pinfunction "1_1") (pintype "passive"))
      (node (ref "C3B") (pin "1") (pinfunction "1_1") (pintype "passive"))
      (node (ref "C4B") (pin "2") (pinfunction "2_2") (pintype "passive"))
      (node (ref "C5B") (pin "2") (pinfunction "2_2") (pintype "passive"))
      (node (ref "C6B") (pin "1") (pinfunction "1_1") (pintype "passive"))
      (node (ref "C7B") (pin "1") (pinfunction "1_1") (pintype "passive"))
      (node (ref "C8B") (pin "1") (pinfunction "1_1") (pintype "passive"))
      (node (ref "C9B") (pin "1") (pinfunction "1_1") (pintype "passive"))
      (node (ref "Q2B") (pin "1") (pinfunction "S_1") (pintype "passive"))
      (node (ref "Q2B") (pin "2") (pinfunction "S_2") (pintype "passive"))
      (node (ref "Q2B") (pin "3") (pinfunction "S_3") (pintype "passive"))
      (node (ref "Q4B") (pin "S") (pinfunction "S_S") (pintype "passive"))
      (node (ref "Q5B") (pin "S") (pinfunction "S_S") (pintype "passive"))
      (node (ref "Q6B") (pin "S") (pinfunction "S_S") (pintype "passive"))
      (node (ref "Q7B") (pin "S") (pinfunction "S_S") (pintype "passive"))
      (node (ref "R16B") (pin "2") (pinfunction "2_2") (pintype "passive"))
      (node (ref "R23B") (pin "2") (pinfunction "2_2") (pintype "passive"))
      (node (ref "R24B") (pin "2") (pinfunction "2_2") (pintype "passive"))
      (node (ref "R26B") (pin "2") (pinfunction "2_2") (pintype "passive"))
      (node (ref "R27B") (pin "2") (pinfunction "2_2") (pintype "passive"))
      (node (ref "R28B") (pin "2") (pinfunction "2_2") (pintype "passive"))
      (node (ref "R29B") (pin "2") (pinfunction "2_2") (pintype "passive"))
      (node (ref "R30B") (pin "2") (pinfunction "2_2") (pintype "passive"))
      (node (ref "R36B") (pin "2") (pinfunction "2_2") (pintype "passive"))
      (node (ref "R7B") (pin "1") (pinfunction "1_1") (pintype "passive"))
      (node (ref "U1B") (pin "0") (pinfunction "T_Pad_0") (pintype "passive"))
      (node (ref "U1B") (pin "10") (pinfunction "PGND_10") (pintype "passive"))
      (node (ref "U1B") (pin "19") (pinfunction "AGND_19") (pintype "passive"))
      (node (ref "U2B") (pin "3") (pinfunction "GND_3") (pintype "passive"))
    )
    (net (code "7") (name "Net-(C1B-Pad2)") (class "Default")
      (node (ref "C1B") (pin "2") (pinfunction "2_2") (pintype "passive"))
      (node (ref "R1B") (pin "2") (pinfunction "2_2") (pintype "passive"))
    )
    (net (code "8") (name "Net-(C14B-Pad2)") (class "Default")
      (node (ref "C14B") (pin "2") (pinfunction "2_2") (pintype "passive"))
      (node (ref "C15B") (pin "2") (pinfunction "2_2") (pintype "passive"))
      (node (ref "C16B") (pin "2") (pinfunction "2_2") (pintype "passive"))
      (node (ref "C2B") (pin "2") (pinfunction "2_2") (pintype "passive"))
      (node (ref "C3B") (pin "2") (pinfunction "2_2") (pintype "passive"))
      (node (ref "C4B") (pin "1") (pinfunction "1_1") (pintype "passive"))
      (node (ref "C5B") (pin "1") (pinfunction "1_1") (pintype "passive"))
      (node (ref "D1B") (pin "A") (pinfunction "A_A") (pintype "passive"))
      (node (ref "Q1B") (pin "5") (pinfunction "D_5") (pintype "passive"))
      (node (ref "Q1B") (pin "6") (pinfunction "D_6") (pintype "passive"))
      (node (ref "Q1B") (pin "7") (pinfunction "D_7") (pintype "passive"))
      (node (ref "Q1B") (pin "8") (pinfunction "D_8") (pintype "passive"))
      (node (ref "R2B") (pin "1") (pinfunction "1_1") (pintype "passive"))
      (node (ref "R4B") (pin "1") (pinfunction "1_1") (pintype "passive"))
      (node (ref "R5B") (pin "1") (pinfunction "1_1") (pintype "passive"))
    )
    (net (code "9") (name "Net-(C17B-Pad2)") (class "Default")
      (node (ref "C17B") (pin "2") (pinfunction "2_2") (pintype "passive"))
      (node (ref "R7B") (pin "2") (pinfunction "2_2") (pintype "passive"))
    )
    (net (code "10") (name "Net-(C29B-Pad1)") (class "Default")
      (node (ref "C29B") (pin "1") (pinfunction "1_1") (pintype "passive"))
      (node (ref "R17B") (pin "1") (pinfunction "1_1") (pintype "passive"))
      (node (ref "R18B") (pin "2") (pinfunction "2_2") (pintype "passive"))
    )
    (net (code "11") (name "Net-(C30B-Pad1)") (class "Default")
      (node (ref "C30B") (pin "1") (pinfunction "1_1") (pintype "passive"))
      (node (ref "R18B") (pin "1") (pinfunction "1_1") (pintype "passive"))
      (node (ref "R19B") (pin "2") (pinfunction "2_2") (pintype "passive"))
      (node (ref "R29B") (pin "1") (pinfunction "1_1") (pintype "passive"))
      (node (ref "R31B") (pin "2") (pinfunction "2_2") (pintype "passive"))
    )
    (net (code "12") (name "Net-(C31B-Pad1)") (class "Default")
      (node (ref "C31B") (pin "1") (pinfunction "1_1") (pintype "passive"))
      (node (ref "R28B") (pin "1") (pinfunction "1_1") (pintype "passive"))
    )
    (net (code "13") (name "Net-(C33B-Pad1)") (class "Default")
      (node (ref "C33B") (pin "1") (pinfunction "1_1") (pintype "passive"))
      (node (ref "Q4B") (pin "D") (pinfunction "D_D") (pintype "passive"))
      (node (ref "R13B") (pin "2") (pinfunction "2_2") (pintype "passive"))
      (node (ref "R15B") (pin "1") (pinfunction "1_1") (pintype "passive"))
      (node (ref "R23B") (pin "1") (pinfunction "1_1") (pintype "passive"))
    )
    (net (code "14") (name "Net-(C37B-Pad2)") (class "Default")
      (node (ref "C37B") (pin "2") (pinfunction "2_2") (pintype "passive"))
      (node (ref "R19B") (pin "1") (pinfunction "1_1") (pintype "passive"))
      (node (ref "R37B") (pin "1") (pinfunction "1_1") (pintype "passive"))
      (node (ref "R38B") (pin "1") (pinfunction "1_1") (pintype "passive"))
    )
    (net (code "15") (name "Net-(D1B-PadK)") (class "Default")
      (node (ref "D1B") (pin "K") (pinfunction "K_K") (pintype "passive"))
      (node (ref "R12B") (pin "2") (pinfunction "2_2") (pintype "passive"))
    )
    (net (code "16") (name "Net-(D2B-PadK)") (class "Default")
      (node (ref "D2B") (pin "K") (pinfunction "K_K") (pintype "passive"))
      (node (ref "R37B") (pin "2") (pinfunction "2_2") (pintype "passive"))
    )
    (net (code "17") (name "Net-(L1B-Pad1)") (class "Default")
      (node (ref "L1B") (pin "1") (pinfunction "1_1") (pintype "passive"))
      (node (ref "R2B") (pin "2") (pinfunction "2_2") (pintype "passive"))
      (node (ref "R4B") (pin "2") (pinfunction "2_2") (pintype "passive"))
      (node (ref "R6B") (pin "1") (pinfunction "1_1") (pintype "passive"))
    )
    (net (code "18") (name "Net-(Q1B-G)") (class "Default")
      (node (ref "Q1B") (pin "4") (pinfunction "G_4") (pintype "passive"))
      (node (ref "R3B") (pin "2") (pinfunction "2_2") (pintype "passive"))
      (node (ref "R9B") (pin "1") (pinfunction "1_1") (pintype "passive"))
    )
    (net (code "19") (name "Net-(Q2B-G)") (class "Default")
      (node (ref "Q2B") (pin "4") (pinfunction "G_4") (pintype "passive"))
      (node (ref "R10B") (pin "2") (pinfunction "2_2") (pintype "passive"))
    )
    (net (code "20") (name "Net-(Q3B-G)") (class "Default")
      (node (ref "Q3B") (pin "4") (pinfunction "G_4") (pintype "passive"))
      (node (ref "R11B") (pin "2") (pinfunction "2_2") (pintype "passive"))
    )
    (net (code "21") (name "Net-(Q4B-PadG)") (class "Default")
      (node (ref "Q4B") (pin "G") (pinfunction "G_G") (pintype "passive"))
      (node (ref "Q5B") (pin "D") (pinfunction "D_D") (pintype "passive"))
      (node (ref "R9B") (pin "2") (pinfunction "2_2") (pintype "passive"))
    )
    (net (code "22") (name "Net-(Q5B-PadG)") (class "Default")
      (node (ref "Q5B") (pin "G") (pinfunction "G_G") (pintype "passive"))
      (node (ref "R22B") (pin "2") (pinfunction "2_2") (pintype "passive"))
      (node (ref "R30B") (pin "1") (pinfunction "1_1") (pintype "passive"))
    )
    (net (code "23") (name "Net-(Q6B-PadD)") (class "Default")
      (node (ref "Q6B") (pin "D") (pinfunction "D_D") (pintype "passive"))
      (node (ref "R32B") (pin "1") (pinfunction "1_1") (pintype "passive"))
    )
    (net (code "24") (name "Net-(Q6B-PadG)") (class "Default")
      (node (ref "Q6B") (pin "G") (pinfunction "G_G") (pintype "passive"))
      (node (ref "Q7B") (pin "D") (pinfunction "D_D") (pintype "passive"))
      (node (ref "R34B") (pin "1") (pinfunction "1_1") (pintype "passive"))
    )
    (net (code "25") (name "Net-(Q7B-PadG)") (class "Default")
      (node (ref "Q7B") (pin "G") (pinfunction "G_G") (pintype "passive"))
      (node (ref "R35B") (pin "2") (pinfunction "2_2") (pintype "passive"))
      (node (ref "R36B") (pin "1") (pinfunction "1_1") (pintype "passive"))
    )
    (net (code "26") (name "Net-(U1B-BIAS)") (class "Default")
      (node (ref "C25B") (pin "1") (pinfunction "1_1") (pintype "passive"))
      (node (ref "R12B") (pin "1") (pinfunction "1_1") (pintype "passive"))
      (node (ref "R13B") (pin "1") (pinfunction "1_1") (pintype "passive"))
      (node (ref "U1B") (pin "8") (pinfunction "BIAS_8") (pintype "passive"))
    )
    (net (code "27") (name "Net-(U1B-COMP)") (class "Default")
      (node (ref "C31B") (pin "2") (pinfunction "2_2") (pintype "passive"))
      (node (ref "C32B") (pin "1") (pinfunction "1_1") (pintype "passive"))
      (node (ref "U1B") (pin "20") (pinfunction "COMP_20") (pintype "passive"))
    )
    (net (code "28") (name "Net-(U1B-CSN)") (class "Default")
      (node (ref "C23B") (pin "2") (pinfunction "2_2") (pintype "passive"))
      (node (ref "R6B") (pin "2") (pinfunction "2_2") (pintype "passive"))
      (node (ref "U1B") (pin "2") (pinfunction "CSN_2") (pintype "passive"))
    )
    (net (code "29") (name "Net-(U1B-CSP)") (class "Default")
      (node (ref "C23B") (pin "1") (pinfunction "1_1") (pintype "passive"))
      (node (ref "R5B") (pin "2") (pinfunction "2_2") (pintype "passive"))
      (node (ref "U1B") (pin "1") (pinfunction "CSP_1") (pintype "passive"))
    )
    (net (code "30") (name "Net-(U1B-HB)") (class "Default")
      (node (ref "C24B") (pin "2") (pinfunction "2_2") (pintype "passive"))
      (node (ref "U1B") (pin "7") (pinfunction "HB_7") (pintype "passive"))
    )
    (net (code "31") (name "Net-(U1B-HO)") (class "Default")
      (node (ref "R11B") (pin "1") (pinfunction "1_1") (pintype "passive"))
      (node (ref "U1B") (pin "5") (pinfunction "HO_5") (pintype "passive"))
    )
    (net (code "32") (name "Net-(U1B-LO)") (class "Default")
      (node (ref "R10B") (pin "1") (pinfunction "1_1") (pintype "passive"))
      (node (ref "U1B") (pin "11") (pinfunction "LO_11") (pintype "passive"))
    )
    (net (code "33") (name "Net-(U1B-MODE)") (class "Default")
      (node (ref "R24B") (pin "1") (pinfunction "1_1") (pintype "passive"))
      (node (ref "U1B") (pin "12") (pinfunction "MODE_12") (pintype "passive"))
    )
    (net (code "34") (name "Net-(U1B-PGOOD)") (class "Default")
      (node (ref "R20B") (pin "2") (pinfunction "2_2") (pintype "passive"))
      (node (ref "U1B") (pin "4") (pinfunction "PGOOD_4") (pintype "passive"))
    )
    (net (code "35") (name "Net-(U1B-RT)") (class "Default")
      (node (ref "R26B") (pin "1") (pinfunction "1_1") (pintype "passive"))
      (node (ref "U1B") (pin "15") (pinfunction "RT_15") (pintype "passive"))
    )
    (net (code "36") (name "Net-(U1B-SS)") (class "Default")
      (node (ref "C36B") (pin "1") (pinfunction "1_1") (pintype "passive"))
      (node (ref "U1B") (pin "17") (pinfunction "SS_17") (pintype "passive"))
    )
    (net (code "37") (name "Net-(U1B-SW)") (class "Default")
      (node (ref "C17B") (pin "1") (pinfunction "1_1") (pintype "passive"))
      (node (ref "C24B") (pin "1") (pinfunction "1_1") (pintype "passive"))
      (node (ref "L1B") (pin "2") (pinfunction "2_2") (pintype "passive"))
      (node (ref "Q2B") (pin "5") (pinfunction "D_5") (pintype "passive"))
      (node (ref "Q2B") (pin "6") (pinfunction "D_6") (pintype "passive"))
      (node (ref "Q2B") (pin "7") (pinfunction "D_7") (pintype "passive"))
      (node (ref "Q2B") (pin "8") (pinfunction "D_8") (pintype "passive"))
      (node (ref "Q3B") (pin "1") (pinfunction "S_1") (pintype "passive"))
      (node (ref "Q3B") (pin "2") (pinfunction "S_2") (pintype "passive"))
      (node (ref "Q3B") (pin "3") (pinfunction "S_3") (pintype "passive"))
      (node (ref "R1B") (pin "1") (pinfunction "1_1") (pintype "passive"))
      (node (ref "U1B") (pin "6") (pinfunction "SW_6") (pintype "passive"))
    )
    (net (code "38") (name "Net-(U1B-SYNC{slash}DITHER{slash}VH)") (class "Default")
      (node (ref "C35B") (pin "1") (pinfunction "1_1") (pintype "passive"))
      (node (ref "R25B") (pin "2") (pinfunction "2_2") (pintype "passive"))
      (node (ref "U1B") (pin "14") (pinfunction "SYNC/DITHER/VH_14") (pintype "passive"))
    )
    (net (code "39") (name "Net-(U1B-TRK)") (class "Default")
      (node (ref "R17B") (pin "2") (pinfunction "2_2") (pintype "passive"))
      (node (ref "TP3B") (pin "1") (pinfunction "1_1") (pintype "passive"))
      (node (ref "U1B") (pin "18") (pinfunction "TRK_18") (pintype "passive"))
    )
    (net (code "40") (name "Net-(U1B-UVLO{slash}EN)") (class "Default")
      (node (ref "R15B") (pin "2") (pinfunction "2_2") (pintype "passive"))
      (node (ref "U1B") (pin "13") (pinfunction "UVLO/EN_13") (pintype "passive"))
    )
    (net (code "41") (name "Net-(U1B-VOUT{slash}SENSE)") (class "Default")
      (node (ref "C27B") (pin "1") (pinfunction "1_1") (pintype "passive"))
      (node (ref "R14B") (pin "2") (pinfunction "2_2") (pintype "passive"))
      (node (ref "U1B") (pin "3") (pinfunction "VOUT/SENSE_3") (pintype "passive"))
    )
    (net (code "42") (name "Net-(U1B-VREF{slash}RANGE)") (class "Default")
      (node (ref "C28B") (pin "1") (pinfunction "1_1") (pintype "passive"))
      (node (ref "R16B") (pin "1") (pinfunction "1_1") (pintype "passive"))
      (node (ref "U1B") (pin "16") (pinfunction "VREF/RANGE_16") (pintype "passive"))
    )
    (net (code "43") (name "Net-(U2B-Y)") (class "Default")
      (node (ref "D2B") (pin "A") (pinfunction "A_A") (pintype "passive"))
      (node (ref "R38B") (pin "2") (pinfunction "2_2") (pintype "passive"))
      (node (ref "TP4B") (pin "1") (pinfunction "1_1") (pintype "passive"))
      (node (ref "U2B") (pin "4") (pinfunction "Y_4") (pintype "passive"))
    )
    (net (code "44") (name "VSys") (class "Default")
      (node (ref "C11B") (pin "1") (pinfunction "1_1") (pintype "passive"))
      (node (ref "C13B") (pin "2") (pinfunction "2_2") (pintype "passive"))
      (node (ref "Q1B") (pin "1") (pinfunction "S_1") (pintype "passive"))
      (node (ref "Q1B") (pin "2") (pinfunction "S_2") (pintype "passive"))
      (node (ref "Q1B") (pin "3") (pinfunction "S_3") (pintype "passive"))
      (node (ref "R3B") (pin "1") (pinfunction "1_1") (pintype "passive"))
      (node (ref "TP1B") (pin "1") (pinfunction "1_1") (pintype "passive"))
    )
    (net (code "45") (name "unconnected-(U2B-NC-Pad1)") (class "Default")
      (node (ref "U2B") (pin "1") (pinfunction "NC_1") (pintype "passive"))
    )
  )
)
